# PIRat-schema.net
KiCad netlist of a schematic drawn in EAGLE
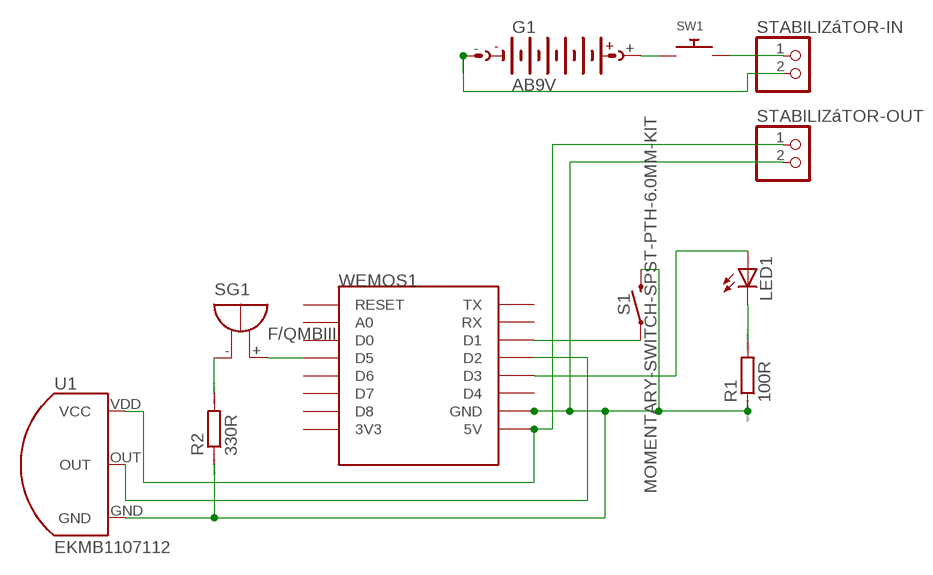
[diagram p0: schematic, sheet 1]

(export (version "E")
  (design (tool "Eeschema 10.0.6"))
  (components
    (comp (ref "G1")
      (value "AB9V")
      (footprint "eagle-import:AB9V")
      (libsource (lib "eagle-import") (part "AB9V"))
    )
    (comp (ref "LED1")
      (value "LED3MM")
      (footprint "eagle-import:LED3MM")
      (libsource (lib "eagle-import") (part "LED3MM"))
    )
    (comp (ref "R1")
      (value "100R")
      (footprint "eagle-import:0207_10")
      (libsource (lib "eagle-import") (part "R0207/10"))
    )
    (comp (ref "R2")
      (value "330R")
      (footprint "eagle-import:0207_10")
      (libsource (lib "eagle-import") (part "R0207/10"))
    )
    (comp (ref "S1")
      (value "MOMENTARY-SWITCH-SPST-PTH-6.0MM-KIT")
      (footprint "eagle-import:TACTILE_SWITCH_PTH_6.0MM_KIT")
      (libsource (lib "eagle-import") (part "MOMENTARY-SWITCH-SPST-PTH-6.0MM-KIT"))
    )
    (comp (ref "SG1")
      (value "F/QMBIII")
      (footprint "eagle-import:F_QMBIII")
      (libsource (lib "eagle-import") (part "F/QMBIII"))
    )
    (comp (ref "STABILIZáTOR-IN")
      (value "PINHD-1X2")
      (footprint "eagle-import:1X02")
      (libsource (lib "eagle-import") (part "PINHD-1X2"))
    )
    (comp (ref "STABILIZáTOR-OUT")
      (value "PINHD-1X2")
      (footprint "eagle-import:1X02")
      (libsource (lib "eagle-import") (part "PINHD-1X2"))
    )
    (comp (ref "SW1")
      (value "SWITCH_PUSHBUTTONEVQ-PE")
      (footprint "eagle-import:TACT_PANA-EVQ")
      (libsource (lib "eagle-import") (part "SWITCH_PUSHBUTTONEVQ-PE"))
    )
    (comp (ref "U1")
      (value "EKMB1107112")
      (footprint "eagle-import:TO-3")
      (libsource (lib "eagle-import") (part "PIR_EKMB1107112"))
    )
    (comp (ref "WEMOS1")
      (value "WEMOS-D1-MINI")
      (footprint "eagle-import:WEMOS-D1-MINI")
      (libsource (lib "eagle-import") (part "WEMOS-D1-MINI"))
    )
  )
  (nets
    (net (code "1") (name "Net-(G1-Pad+)") (class "Default")
      (node (ref "G1") (pin "+") (pinfunction "+_+") (pintype "passive"))
      (node (ref "SW1") (pin "P$1") (pinfunction "P$1_P$1") (pintype "passive"))
    )
    (net (code "2") (name "Net-(G1-Pad-)") (class "Default")
      (node (ref "G1") (pin "-") (pinfunction "-_-") (pintype "passive"))
      (node (ref "STABILIZáTOR-IN") (pin "2") (pinfunction "2_2") (pintype "passive"))
    )
    (net (code "3") (name "Net-(LED1-C)") (class "Default")
      (node (ref "LED1") (pin "K") (pinfunction "C_K") (pintype "passive"))
      (node (ref "R1") (pin "2") (pinfunction "2_2") (pintype "passive"))
    )
    (net (code "4") (name "Net-(LED1-PadA)") (class "Default")
      (node (ref "LED1") (pin "A") (pinfunction "A_A") (pintype "passive"))
      (node (ref "WEMOS1") (pin "D3") (pinfunction "D3_D3") (pintype "bidirectional"))
    )
    (net (code "5") (name "Net-(S1-2)") (class "Default")
      (node (ref "R1") (pin "1") (pinfunction "1_1") (pintype "passive"))
      (node (ref "R2") (pin "1") (pinfunction "1_1") (pintype "passive"))
      (node (ref "S1") (pin "3") (pinfunction "2_3") (pintype "passive"))
      (node (ref "STABILIZáTOR-OUT") (pin "2") (pinfunction "2_2") (pintype "passive"))
      (node (ref "U1") (pin "GND") (pinfunction "GND_GND") (pintype "bidirectional"))
      (node (ref "WEMOS1") (pin "GND") (pinfunction "GND_GND") (pintype "bidirectional"))
    )
    (net (code "6") (name "Net-(S1-Pad1)") (class "Default")
      (node (ref "S1") (pin "1") (pinfunction "1_1") (pintype "passive"))
      (node (ref "WEMOS1") (pin "D1") (pinfunction "D1_D1") (pintype "bidirectional"))
    )
    (net (code "7") (name "Net-(SG1-+)") (class "Default")
      (node (ref "R2") (pin "2") (pinfunction "2_2") (pintype "passive"))
      (node (ref "SG1") (pin "-") (pinfunction "+_-") (pintype "passive"))
    )
    (net (code "8") (name "Net-(SG1--)") (class "Default")
      (node (ref "SG1") (pin "+") (pinfunction "-_+") (pintype "passive"))
      (node (ref "WEMOS1") (pin "D5") (pinfunction "D5_D5") (pintype "bidirectional"))
    )
    (net (code "9") (name "Net-(STABILIZáTOR-IN-Pad1)") (class "Default")
      (node (ref "STABILIZáTOR-IN") (pin "1") (pinfunction "1_1") (pintype "passive"))
      (node (ref "SW1") (pin "P$2") (pinfunction "P$2_P$2") (pintype "passive"))
    )
    (net (code "10") (name "Net-(U1-PadOUT)") (class "Default")
      (node (ref "U1") (pin "OUT") (pinfunction "OUT_OUT") (pintype "bidirectional"))
      (node (ref "WEMOS1") (pin "D2") (pinfunction "D2_D2") (pintype "bidirectional"))
    )
    (net (code "11") (name "Net-(U1-VCC)") (class "Default")
      (node (ref "STABILIZáTOR-OUT") (pin "1") (pinfunction "1_1") (pintype "passive"))
      (node (ref "U1") (pin "VDD") (pinfunction "VCC_VDD") (pintype "bidirectional"))
      (node (ref "WEMOS1") (pin "5V") (pinfunction "5V_5V") (pintype "bidirectional"))
    )
    (net (code "12") (name "unconnected-(WEMOS1-Pad3V3)") (class "Default")
      (node (ref "WEMOS1") (pin "3V3") (pinfunction "3V3_3V3") (pintype "bidirectional"))
    )
    (net (code "13") (name "unconnected-(WEMOS1-PadA0)") (class "Default")
      (node (ref "WEMOS1") (pin "A0") (pinfunction "A0_A0") (pintype "bidirectional"))
    )
    (net (code "14") (name "unconnected-(WEMOS1-PadD0)") (class "Default")
      (node (ref "WEMOS1") (pin "D0") (pinfunction "D0_D0") (pintype "bidirectional"))
    )
    (net (code "15") (name "unconnected-(WEMOS1-PadD4)") (class "Default")
      (node (ref "WEMOS1") (pin "D4") (pinfunction "D4_D4") (pintype "bidirectional"))
    )
    (net (code "16") (name "unconnected-(WEMOS1-PadD6)") (class "Default")
      (node (ref "WEMOS1") (pin "D6") (pinfunction "D6_D6") (pintype "bidirectional"))
    )
    (net (code "17") (name "unconnected-(WEMOS1-PadD7)") (class "Default")
      (node (ref "WEMOS1") (pin "D7") (pinfunction "D7_D7") (pintype "bidirectional"))
    )
    (net (code "18") (name "unconnected-(WEMOS1-PadD8)") (class "Default")
      (node (ref "WEMOS1") (pin "D8") (pinfunction "D8_D8") (pintype "bidirectional"))
    )
    (net (code "19") (name "unconnected-(WEMOS1-PadRESET)") (class "Default")
      (node (ref "WEMOS1") (pin "RESET") (pinfunction "RESET_RESET") (pintype "bidirectional"))
    )
    (net (code "20") (name "unconnected-(WEMOS1-PadRX)") (class "Default")
      (node (ref "WEMOS1") (pin "RX") (pinfunction "RX_RX") (pintype "bidirectional"))
    )
    (net (code "21") (name "unconnected-(WEMOS1-PadTX)") (class "Default")
      (node (ref "WEMOS1") (pin "TX") (pinfunction "TX_TX") (pintype "bidirectional"))
    )
  )
)
